# CHARGING_IC.net
KiCad netlist of a schematic drawn in Altium Designer
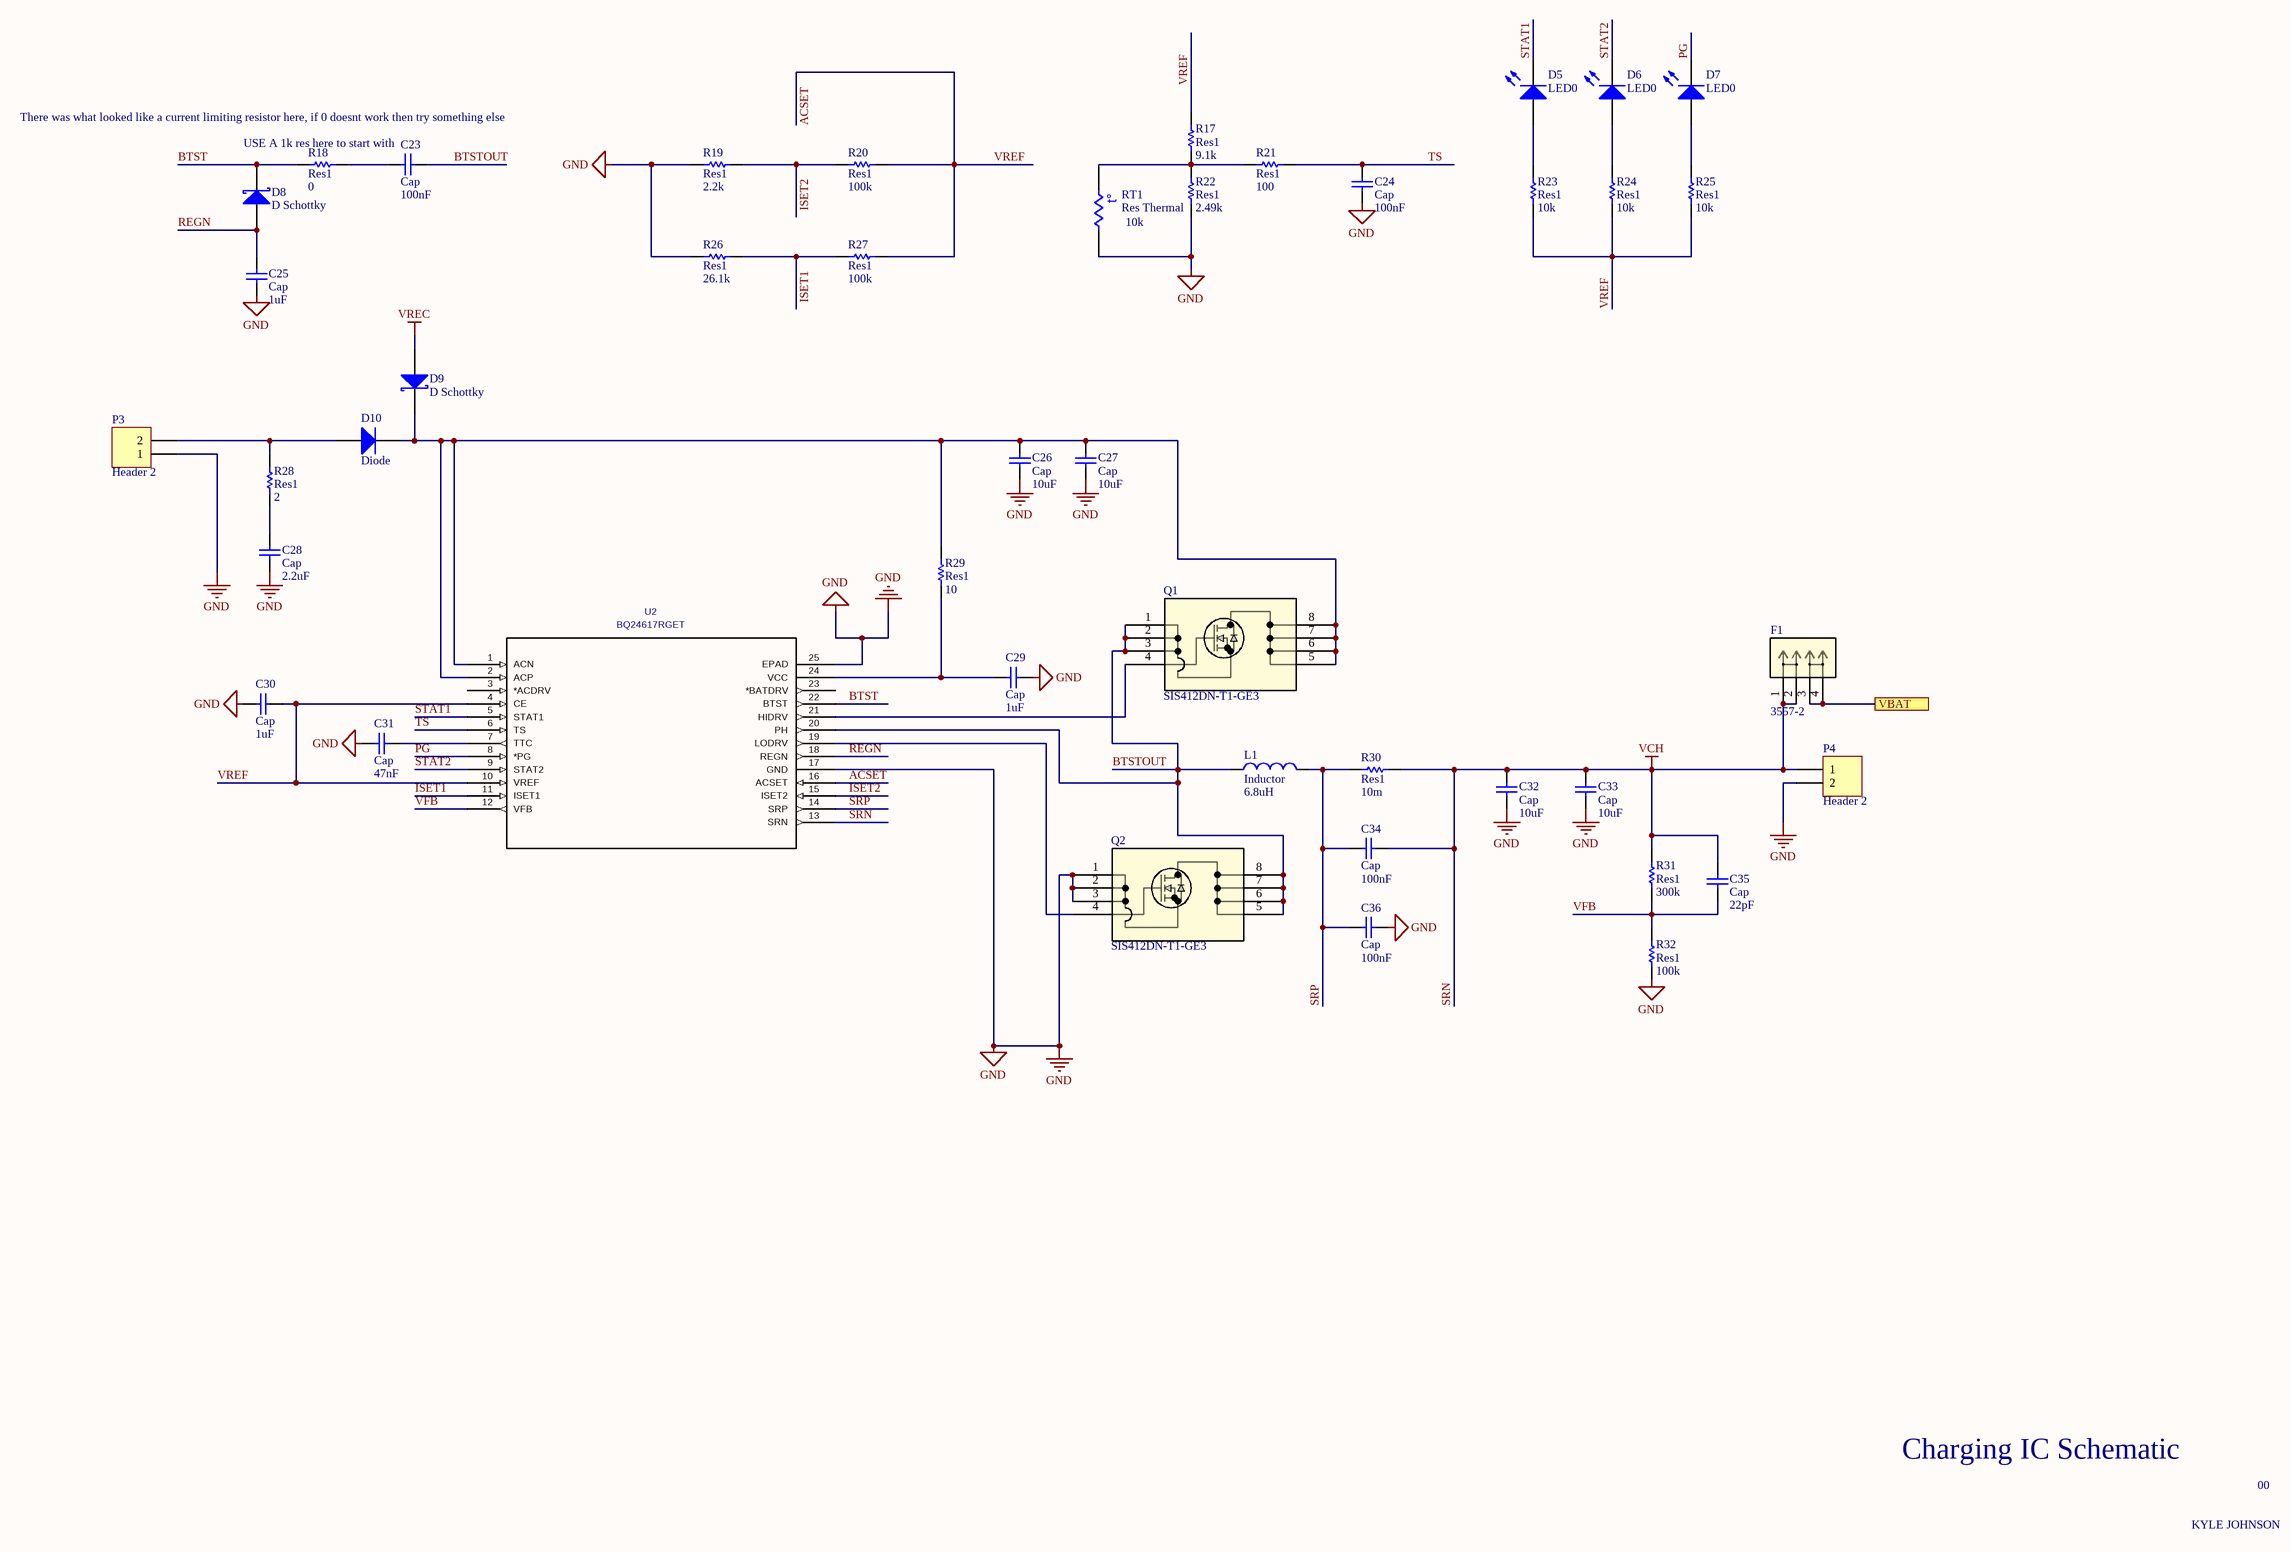
[diagram p0: CHARGING IC.SchDoc]

(export (version "E")
  (design (tool "Eeschema 10.0.6"))
  (components
    (comp (ref "C23")
      (value "Cap")
      (footprint "0402-A")
      (description "Capacitor")
      (fields (field (name "ALTIUM_VALUE") "100nF") (field (name "PUBLISHER") "Altium Limited"))
      (libsource (lib "Miscellaneous Devices") (part "Cap"))
    )
    (comp (ref "C24")
      (value "Cap")
      (footprint "0402-A")
      (description "Capacitor")
      (fields (field (name "ALTIUM_VALUE") "100nF") (field (name "PUBLISHER") "Altium Limited"))
      (libsource (lib "Miscellaneous Devices") (part "Cap"))
    )
    (comp (ref "C25")
      (value "Cap")
      (footprint "0402-A")
      (description "Capacitor")
      (fields (field (name "ALTIUM_VALUE") "1uF") (field (name "PUBLISHER") "Altium Limited"))
      (libsource (lib "Miscellaneous Devices") (part "Cap"))
    )
    (comp (ref "C26")
      (value "Cap")
      (footprint "6-0805_M")
      (description "Capacitor")
      (fields (field (name "ALTIUM_VALUE") "10uF") (field (name "PUBLISHER") "Altium Limited"))
      (libsource (lib "Miscellaneous Devices") (part "Cap"))
    )
    (comp (ref "C27")
      (value "Cap")
      (footprint "6-0805_M")
      (description "Capacitor")
      (fields (field (name "ALTIUM_VALUE") "10uF") (field (name "PUBLISHER") "Altium Limited"))
      (libsource (lib "Miscellaneous Devices") (part "Cap"))
    )
    (comp (ref "C28")
      (value "Cap")
      (footprint "1608[0603]")
      (description "Capacitor")
      (fields (field (name "ALTIUM_VALUE") "2.2uF") (field (name "PUBLISHER") "Altium Limited"))
      (libsource (lib "Miscellaneous Devices") (part "Cap"))
    )
    (comp (ref "C29")
      (value "Cap")
      (footprint "0402-A")
      (description "Capacitor")
      (fields (field (name "ALTIUM_VALUE") "1uF") (field (name "PUBLISHER") "Altium Limited"))
      (libsource (lib "Miscellaneous Devices") (part "Cap"))
    )
    (comp (ref "C30")
      (value "Cap")
      (footprint "0402-A")
      (description "Capacitor")
      (fields (field (name "ALTIUM_VALUE") "1uF") (field (name "PUBLISHER") "Altium Limited"))
      (libsource (lib "Miscellaneous Devices") (part "Cap"))
    )
    (comp (ref "C31")
      (value "Cap")
      (footprint "0402-A")
      (description "Capacitor")
      (fields (field (name "ALTIUM_VALUE") "47nF") (field (name "PUBLISHER") "Altium Limited"))
      (libsource (lib "Miscellaneous Devices") (part "Cap"))
    )
    (comp (ref "C32")
      (value "Cap")
      (footprint "6-0805_M")
      (description "Capacitor")
      (fields (field (name "ALTIUM_VALUE") "10uF") (field (name "PUBLISHER") "Altium Limited"))
      (libsource (lib "Miscellaneous Devices") (part "Cap"))
    )
    (comp (ref "C33")
      (value "Cap")
      (footprint "6-0805_M")
      (description "Capacitor")
      (fields (field (name "ALTIUM_VALUE") "10uF") (field (name "PUBLISHER") "Altium Limited"))
      (libsource (lib "Miscellaneous Devices") (part "Cap"))
    )
    (comp (ref "C34")
      (value "Cap")
      (footprint "0402-A")
      (description "Capacitor")
      (fields (field (name "ALTIUM_VALUE") "100nF") (field (name "PUBLISHER") "Altium Limited"))
      (libsource (lib "Miscellaneous Devices") (part "Cap"))
    )
    (comp (ref "C35")
      (value "Cap")
      (footprint "0402-A")
      (description "Capacitor")
      (fields (field (name "ALTIUM_VALUE") "22pF") (field (name "PUBLISHER") "Altium Limited"))
      (libsource (lib "Miscellaneous Devices") (part "Cap"))
    )
    (comp (ref "C36")
      (value "Cap")
      (footprint "0402-A")
      (description "Capacitor")
      (fields (field (name "ALTIUM_VALUE") "100nF") (field (name "PUBLISHER") "Altium Limited"))
      (libsource (lib "Miscellaneous Devices") (part "Cap"))
    )
    (comp (ref "D5")
      (value "LED0")
      (footprint "1608[0603]")
      (fields (field (name "PUBLISHER") "Altium Limited"))
      (libsource (lib "Miscellaneous Devices") (part "LED0"))
    )
    (comp (ref "D6")
      (value "LED0")
      (footprint "1608[0603]")
      (fields (field (name "PUBLISHER") "Altium Limited"))
      (libsource (lib "Miscellaneous Devices") (part "LED0"))
    )
    (comp (ref "D7")
      (value "LED0")
      (footprint "1608[0603]")
      (fields (field (name "PUBLISHER") "Altium Limited"))
      (libsource (lib "Miscellaneous Devices") (part "LED0"))
    )
    (comp (ref "D8")
      (value "D Schottky")
      (footprint "425")
      (description "Schottky Diode")
      (fields (field (name "PUBLISHER") "Altium Limited"))
      (libsource (lib "Miscellaneous Devices") (part "D Schottky"))
    )
    (comp (ref "D9")
      (value "D Schottky")
      (footprint "425")
      (description "Schottky Diode")
      (fields (field (name "PUBLISHER") "Altium Limited"))
      (libsource (lib "Miscellaneous Devices") (part "D Schottky"))
    )
    (comp (ref "D10")
      (value "Diode")
      (footprint "X3-WLB1608-2")
      (description "Default Diode")
      (fields (field (name "PUBLISHER") "Altium Limited"))
      (libsource (lib "Miscellaneous Devices") (part "Diode"))
    )
    (comp (ref "F1")
      (value "3557-2")
      (footprint "CONN_3557-2_KEY")
      (description "No Description Available")
      (fields (field (name "COPYRIGHT") "Copyright (C) 2018 Accelerated Designs. All rights reserved"))
      (libsource (lib "3557-2") (part "3557-2"))
    )
    (comp (ref "L1")
      (value "Inductor")
      (footprint "IHLP2525CZER6R8MA1")
      (fields (field (name "ALTIUM_VALUE") "6.8uH") (field (name "PUBLISHER") "Altium Limited"))
      (libsource (lib "Miscellaneous Devices") (part "Inductor"))
    )
    (comp (ref "P3")
      (value "Header 2")
      (footprint "2-1445096-2")
      (description "Header, 2-Pin")
      (fields (field (name "PUBLISHER") "Altium Limited"))
      (libsource (lib "") (part "Header 2_1"))
    )
    (comp (ref "P4")
      (value "Header 2")
      (footprint "2-1445096-2")
      (description "Header, 2-Pin")
      (fields (field (name "PUBLISHER") "Altium Limited"))
      (libsource (lib "Miscellaneous Connectors") (part "Header 2"))
    )
    (comp (ref "Q1")
      (value "SIS412DN-T1-GE3")
      (footprint "POWERPAK_1212-8")
      (description "No Description Available")
      (fields (field (name "COPYRIGHT") "Copyright (C) 2018 Accelerated Designs. All rights reserved"))
      (libsource (lib "SIS412DN-T1-GE3") (part "SIS412DN-T1-GE3"))
    )
    (comp (ref "Q2")
      (value "SIS412DN-T1-GE3")
      (footprint "POWERPAK_1212-8")
      (description "No Description Available")
      (fields (field (name "COPYRIGHT") "Copyright (C) 2018 Accelerated Designs. All rights reserved"))
      (libsource (lib "SIS412DN-T1-GE3") (part "SIS412DN-T1-GE3"))
    )
    (comp (ref "R17")
      (value "Res1")
      (footprint "0402-A")
      (description "Resistor")
      (fields (field (name "ALTIUM_VALUE") "9.1k") (field (name "PUBLISHER") "Altium Limited"))
      (libsource (lib "Miscellaneous Devices") (part "Res1"))
    )
    (comp (ref "R18")
      (value "Res1")
      (footprint "0402-A")
      (description "Resistor")
      (fields (field (name "ALTIUM_VALUE") "0") (field (name "PUBLISHER") "Altium Limited"))
      (libsource (lib "Miscellaneous Devices") (part "Res1"))
    )
    (comp (ref "R19")
      (value "Res1")
      (footprint "0402-A")
      (description "Resistor")
      (fields (field (name "ALTIUM_VALUE") "2.2k") (field (name "PUBLISHER") "Altium Limited"))
      (libsource (lib "Miscellaneous Devices") (part "Res1"))
    )
    (comp (ref "R20")
      (value "Res1")
      (footprint "0402-A")
      (description "Resistor")
      (fields (field (name "ALTIUM_VALUE") "100k") (field (name "PUBLISHER") "Altium Limited"))
      (libsource (lib "Miscellaneous Devices") (part "Res1"))
    )
    (comp (ref "R21")
      (value "Res1")
      (footprint "0402-A")
      (description "Resistor")
      (fields (field (name "ALTIUM_VALUE") "100") (field (name "PUBLISHER") "Altium Limited"))
      (libsource (lib "Miscellaneous Devices") (part "Res1"))
    )
    (comp (ref "R22")
      (value "Res1")
      (footprint "0402-A")
      (description "Resistor")
      (fields (field (name "ALTIUM_VALUE") "2.49k") (field (name "PUBLISHER") "Altium Limited"))
      (libsource (lib "Miscellaneous Devices") (part "Res1"))
    )
    (comp (ref "R23")
      (value "Res1")
      (footprint "0402-A")
      (description "Resistor")
      (fields (field (name "ALTIUM_VALUE") "10k") (field (name "PUBLISHER") "Altium Limited"))
      (libsource (lib "Miscellaneous Devices") (part "Res1"))
    )
    (comp (ref "R24")
      (value "Res1")
      (footprint "0402-A")
      (description "Resistor")
      (fields (field (name "ALTIUM_VALUE") "10k") (field (name "PUBLISHER") "Altium Limited"))
      (libsource (lib "Miscellaneous Devices") (part "Res1"))
    )
    (comp (ref "R25")
      (value "Res1")
      (footprint "0402-A")
      (description "Resistor")
      (fields (field (name "ALTIUM_VALUE") "10k") (field (name "PUBLISHER") "Altium Limited"))
      (libsource (lib "Miscellaneous Devices") (part "Res1"))
    )
    (comp (ref "R26")
      (value "Res1")
      (footprint "0402-A")
      (description "Resistor")
      (fields (field (name "ALTIUM_VALUE") "26.1k") (field (name "PUBLISHER") "Altium Limited"))
      (libsource (lib "Miscellaneous Devices") (part "Res1"))
    )
    (comp (ref "R27")
      (value "Res1")
      (footprint "0402-A")
      (description "Resistor")
      (fields (field (name "ALTIUM_VALUE") "100k") (field (name "PUBLISHER") "Altium Limited"))
      (libsource (lib "Miscellaneous Devices") (part "Res1"))
    )
    (comp (ref "R28")
      (value "Res1")
      (footprint "6-0805_M")
      (description "Resistor")
      (fields (field (name "ALTIUM_VALUE") "2") (field (name "PUBLISHER") "Altium Limited"))
      (libsource (lib "Miscellaneous Devices") (part "Res1"))
    )
    (comp (ref "R29")
      (value "Res1")
      (footprint "0402-A")
      (description "Resistor")
      (fields (field (name "ALTIUM_VALUE") "10") (field (name "PUBLISHER") "Altium Limited"))
      (libsource (lib "Miscellaneous Devices") (part "Res1"))
    )
    (comp (ref "R30")
      (value "Res1")
      (footprint "6-0805_M")
      (description "Resistor")
      (fields (field (name "ALTIUM_VALUE") "10m") (field (name "PUBLISHER") "Altium Limited"))
      (libsource (lib "Miscellaneous Devices") (part "Res1"))
    )
    (comp (ref "R31")
      (value "Res1")
      (footprint "0402-A")
      (description "Resistor")
      (fields (field (name "ALTIUM_VALUE") "300k") (field (name "PUBLISHER") "Altium Limited"))
      (libsource (lib "Miscellaneous Devices") (part "Res1"))
    )
    (comp (ref "R32")
      (value "Res1")
      (footprint "0402-A")
      (description "Resistor")
      (fields (field (name "ALTIUM_VALUE") "100k") (field (name "PUBLISHER") "Altium Limited"))
      (libsource (lib "Miscellaneous Devices") (part "Res1"))
    )
    (comp (ref "RT1")
      (value "Res Thermal")
      (footprint "1608[0603]")
      (description "Thermistor")
      (fields (field (name "ALTIUM_VALUE") "10k") (field (name "PUBLISHER") "Altium Limited"))
      (libsource (lib "Miscellaneous Devices") (part "Res Thermal"))
    )
    (comp (ref "U2")
      (value "BQ24617RGET")
      (footprint "RGE24_2P45X2P45")
      (fields (field (name "MANUFACTURER") "Texas Instruments"))
      (libsource (lib "BQ24617RGET") (part "BQ24617RGET"))
    )
  )
  (nets
    (net (code "1") (name "/ACSET") (class "Default")
      (node (ref "C30") (pin "1") (pinfunction "1_1") (pintype "passive"))
      (node (ref "R17") (pin "2") (pinfunction "2_2") (pintype "passive"))
      (node (ref "R20") (pin "2") (pinfunction "2_2") (pintype "passive"))
      (node (ref "R23") (pin "1") (pinfunction "1_1") (pintype "passive"))
      (node (ref "R24") (pin "1") (pinfunction "1_1") (pintype "passive"))
      (node (ref "R25") (pin "1") (pinfunction "1_1") (pintype "passive"))
      (node (ref "R27") (pin "2") (pinfunction "2_2") (pintype "passive"))
      (node (ref "U2") (pin "10") (pinfunction "VREF_10") (pintype "input"))
      (node (ref "U2") (pin "16") (pinfunction "ACSET_16") (pintype "input"))
      (node (ref "U2") (pin "4") (pinfunction "CE_4") (pintype "input"))
    )
    (net (code "2") (name "/BTST") (class "Default")
      (node (ref "D8") (pin "2") (pinfunction "K_2") (pintype "passive"))
      (node (ref "R18") (pin "1") (pinfunction "1_1") (pintype "passive"))
      (node (ref "U2") (pin "22") (pinfunction "BTST_22") (pintype "output"))
    )
    (net (code "3") (name "/BTSTOUT") (class "Default")
      (node (ref "C23") (pin "2") (pinfunction "2_2") (pintype "passive"))
      (node (ref "L1") (pin "1") (pinfunction "1_1") (pintype "passive"))
      (node (ref "Q1") (pin "1") (pinfunction "S_1") (pintype "passive"))
      (node (ref "Q1") (pin "2") (pinfunction "S_2") (pintype "passive"))
      (node (ref "Q1") (pin "3") (pinfunction "S_3") (pintype "passive"))
      (node (ref "Q2") (pin "5") (pinfunction "D_5") (pintype "passive"))
      (node (ref "Q2") (pin "6") (pinfunction "D_6") (pintype "passive"))
      (node (ref "Q2") (pin "7") (pinfunction "D_7") (pintype "passive"))
      (node (ref "Q2") (pin "8") (pinfunction "D_8") (pintype "passive"))
      (node (ref "U2") (pin "20") (pinfunction "PH_20") (pintype "output"))
    )
    (net (code "4") (name "/ISET1") (class "Default")
      (node (ref "R26") (pin "2") (pinfunction "2_2") (pintype "passive"))
      (node (ref "R27") (pin "1") (pinfunction "1_1") (pintype "passive"))
      (node (ref "U2") (pin "11") (pinfunction "ISET1_11") (pintype "input"))
    )
    (net (code "5") (name "/ISET2") (class "Default")
      (node (ref "R19") (pin "2") (pinfunction "2_2") (pintype "passive"))
      (node (ref "R20") (pin "1") (pinfunction "1_1") (pintype "passive"))
      (node (ref "U2") (pin "15") (pinfunction "ISET2_15") (pintype "input"))
    )
    (net (code "6") (name "/PG") (class "Default")
      (node (ref "D7") (pin "2") (pinfunction "K_2") (pintype "passive"))
      (node (ref "U2") (pin "8") (pinfunction "*PG_8") (pintype "input"))
    )
    (net (code "7") (name "/REGN") (class "Default")
      (node (ref "C25") (pin "2") (pinfunction "2_2") (pintype "passive"))
      (node (ref "D8") (pin "1") (pinfunction "A_1") (pintype "passive"))
      (node (ref "U2") (pin "18") (pinfunction "REGN_18") (pintype "output"))
    )
    (net (code "8") (name "/SRP") (class "Default")
      (node (ref "C34") (pin "2") (pinfunction "2_2") (pintype "passive"))
      (node (ref "C36") (pin "1") (pinfunction "1_1") (pintype "passive"))
      (node (ref "L1") (pin "2") (pinfunction "2_2") (pintype "passive"))
      (node (ref "R30") (pin "1") (pinfunction "1_1") (pintype "passive"))
      (node (ref "U2") (pin "14") (pinfunction "SRP_14") (pintype "output"))
    )
    (net (code "9") (name "/STAT1") (class "Default")
      (node (ref "D5") (pin "2") (pinfunction "K_2") (pintype "passive"))
      (node (ref "U2") (pin "5") (pinfunction "STAT1_5") (pintype "input"))
    )
    (net (code "10") (name "/STAT2") (class "Default")
      (node (ref "D6") (pin "2") (pinfunction "K_2") (pintype "passive"))
      (node (ref "U2") (pin "9") (pinfunction "STAT2_9") (pintype "input"))
    )
    (net (code "11") (name "/TS") (class "Default")
      (node (ref "C24") (pin "2") (pinfunction "2_2") (pintype "passive"))
      (node (ref "R21") (pin "2") (pinfunction "2_2") (pintype "passive"))
      (node (ref "U2") (pin "6") (pinfunction "TS_6") (pintype "input"))
    )
    (net (code "12") (name "/VBAT") (class "Default")
      (node (ref "F1") (pin "3") (pinfunction "3_3") (pintype "passive"))
      (node (ref "F1") (pin "4") (pinfunction "4_4") (pintype "passive"))
    )
    (net (code "13") (name "/VFB") (class "Default")
      (node (ref "C35") (pin "2") (pinfunction "2_2") (pintype "passive"))
      (node (ref "R31") (pin "1") (pinfunction "1_1") (pintype "passive"))
      (node (ref "R32") (pin "2") (pinfunction "2_2") (pintype "passive"))
      (node (ref "U2") (pin "12") (pinfunction "VFB_12") (pintype "output"))
    )
    (net (code "14") (name "GND") (class "Default")
      (node (ref "C24") (pin "1") (pinfunction "1_1") (pintype "passive"))
      (node (ref "C25") (pin "1") (pinfunction "1_1") (pintype "passive"))
      (node (ref "C26") (pin "1") (pinfunction "1_1") (pintype "passive"))
      (node (ref "C27") (pin "1") (pinfunction "1_1") (pintype "passive"))
      (node (ref "C28") (pin "1") (pinfunction "1_1") (pintype "passive"))
      (node (ref "C29") (pin "2") (pinfunction "2_2") (pintype "passive"))
      (node (ref "C30") (pin "2") (pinfunction "2_2") (pintype "passive"))
      (node (ref "C31") (pin "1") (pinfunction "1_1") (pintype "passive"))
      (node (ref "C32") (pin "1") (pinfunction "1_1") (pintype "passive"))
      (node (ref "C33") (pin "1") (pinfunction "1_1") (pintype "passive"))
      (node (ref "C36") (pin "2") (pinfunction "2_2") (pintype "passive"))
      (node (ref "P3") (pin "1") (pinfunction "1_1") (pintype "passive"))
      (node (ref "P4") (pin "2") (pinfunction "2_2") (pintype "passive"))
      (node (ref "Q2") (pin "1") (pinfunction "S_1") (pintype "passive"))
      (node (ref "Q2") (pin "2") (pinfunction "S_2") (pintype "passive"))
      (node (ref "Q2") (pin "3") (pinfunction "S_3") (pintype "passive"))
      (node (ref "R19") (pin "1") (pinfunction "1_1") (pintype "passive"))
      (node (ref "R22") (pin "1") (pinfunction "1_1") (pintype "passive"))
      (node (ref "R26") (pin "1") (pinfunction "1_1") (pintype "passive"))
      (node (ref "R32") (pin "1") (pinfunction "1_1") (pintype "passive"))
      (node (ref "RT1") (pin "2") (pinfunction "2_2") (pintype "passive"))
      (node (ref "U2") (pin "17") (pinfunction "GND_17") (pintype "power_in"))
      (node (ref "U2") (pin "25") (pinfunction "EPAD_25") (pintype "power_in"))
    )
    (net (code "15") (name "Net-(C23-Pad1)") (class "Default")
      (node (ref "C23") (pin "1") (pinfunction "1_1") (pintype "passive"))
      (node (ref "R18") (pin "2") (pinfunction "2_2") (pintype "passive"))
    )
    (net (code "16") (name "Net-(C28-Pad2)") (class "Default")
      (node (ref "C28") (pin "2") (pinfunction "2_2") (pintype "passive"))
      (node (ref "R28") (pin "1") (pinfunction "1_1") (pintype "passive"))
    )
    (net (code "17") (name "Net-(D5-A)") (class "Default")
      (node (ref "D5") (pin "1") (pinfunction "A_1") (pintype "passive"))
      (node (ref "R23") (pin "2") (pinfunction "2_2") (pintype "passive"))
    )
    (net (code "18") (name "Net-(D6-A)") (class "Default")
      (node (ref "D6") (pin "1") (pinfunction "A_1") (pintype "passive"))
      (node (ref "R24") (pin "2") (pinfunction "2_2") (pintype "passive"))
    )
    (net (code "19") (name "Net-(D7-A)") (class "Default")
      (node (ref "D7") (pin "1") (pinfunction "A_1") (pintype "passive"))
      (node (ref "R25") (pin "2") (pinfunction "2_2") (pintype "passive"))
    )
    (net (code "20") (name "Net-(D10-A)") (class "Default")
      (node (ref "D10") (pin "1") (pinfunction "A_1") (pintype "passive"))
      (node (ref "P3") (pin "2") (pinfunction "2_2") (pintype "passive"))
      (node (ref "R28") (pin "2") (pinfunction "2_2") (pintype "passive"))
    )
    (net (code "21") (name "Net-(D10-K)") (class "Default")
      (node (ref "C26") (pin "2") (pinfunction "2_2") (pintype "passive"))
      (node (ref "C27") (pin "2") (pinfunction "2_2") (pintype "passive"))
      (node (ref "D10") (pin "2") (pinfunction "K_2") (pintype "passive"))
      (node (ref "D9") (pin "2") (pinfunction "K_2") (pintype "passive"))
      (node (ref "Q1") (pin "5") (pinfunction "D_5") (pintype "passive"))
      (node (ref "Q1") (pin "6") (pinfunction "D_6") (pintype "passive"))
      (node (ref "Q1") (pin "7") (pinfunction "D_7") (pintype "passive"))
      (node (ref "Q1") (pin "8") (pinfunction "D_8") (pintype "passive"))
      (node (ref "R29") (pin "2") (pinfunction "2_2") (pintype "passive"))
      (node (ref "U2") (pin "1") (pinfunction "ACN_1") (pintype "input"))
      (node (ref "U2") (pin "2") (pinfunction "ACP_2") (pintype "input"))
    )
    (net (code "22") (name "Net-(Q1-G)") (class "Default")
      (node (ref "Q1") (pin "4") (pinfunction "G_4") (pintype "passive"))
      (node (ref "U2") (pin "21") (pinfunction "HIDRV_21") (pintype "output"))
    )
    (net (code "23") (name "Net-(Q2-G)") (class "Default")
      (node (ref "Q2") (pin "4") (pinfunction "G_4") (pintype "passive"))
      (node (ref "U2") (pin "19") (pinfunction "LODRV_19") (pintype "output"))
    )
    (net (code "24") (name "Net-(R17-Pad1)") (class "Default")
      (node (ref "R17") (pin "1") (pinfunction "1_1") (pintype "passive"))
      (node (ref "R21") (pin "1") (pinfunction "1_1") (pintype "passive"))
      (node (ref "R22") (pin "2") (pinfunction "2_2") (pintype "passive"))
      (node (ref "RT1") (pin "1") (pinfunction "1_1") (pintype "passive"))
    )
    (net (code "25") (name "Net-(U2-TTC)") (class "Default")
      (node (ref "C31") (pin "2") (pinfunction "2_2") (pintype "passive"))
      (node (ref "U2") (pin "7") (pinfunction "TTC_7") (pintype "output"))
    )
    (net (code "26") (name "Net-(U2-VCC)") (class "Default")
      (node (ref "C29") (pin "1") (pinfunction "1_1") (pintype "passive"))
      (node (ref "R29") (pin "1") (pinfunction "1_1") (pintype "passive"))
      (node (ref "U2") (pin "24") (pinfunction "VCC_24") (pintype "power_in"))
    )
    (net (code "27") (name "VCH") (class "Default")
      (node (ref "C32") (pin "2") (pinfunction "2_2") (pintype "passive"))
      (node (ref "C33") (pin "2") (pinfunction "2_2") (pintype "passive"))
      (node (ref "C34") (pin "1") (pinfunction "1_1") (pintype "passive"))
      (node (ref "C35") (pin "1") (pinfunction "1_1") (pintype "passive"))
      (node (ref "F1") (pin "1") (pinfunction "1_1") (pintype "passive"))
      (node (ref "F1") (pin "2") (pinfunction "2_2") (pintype "passive"))
      (node (ref "P4") (pin "1") (pinfunction "1_1") (pintype "passive"))
      (node (ref "R30") (pin "2") (pinfunction "2_2") (pintype "passive"))
      (node (ref "R31") (pin "2") (pinfunction "2_2") (pintype "passive"))
      (node (ref "U2") (pin "13") (pinfunction "SRN_13") (pintype "output"))
    )
    (net (code "28") (name "VREC") (class "Default")
      (node (ref "D9") (pin "1") (pinfunction "A_1") (pintype "passive"))
    )
    (net (code "29") (name "unconnected-(U2-*ACDRV-Pad3)") (class "Default")
      (node (ref "U2") (pin "3") (pinfunction "*ACDRV_3") (pintype "input"))
    )
    (net (code "30") (name "unconnected-(U2-*BATDRV-Pad23)") (class "Default")
      (node (ref "U2") (pin "23") (pinfunction "*BATDRV_23") (pintype "output"))
    )
  )
)
